# upper.net
KiCad netlist of a schematic drawn in EAGLE
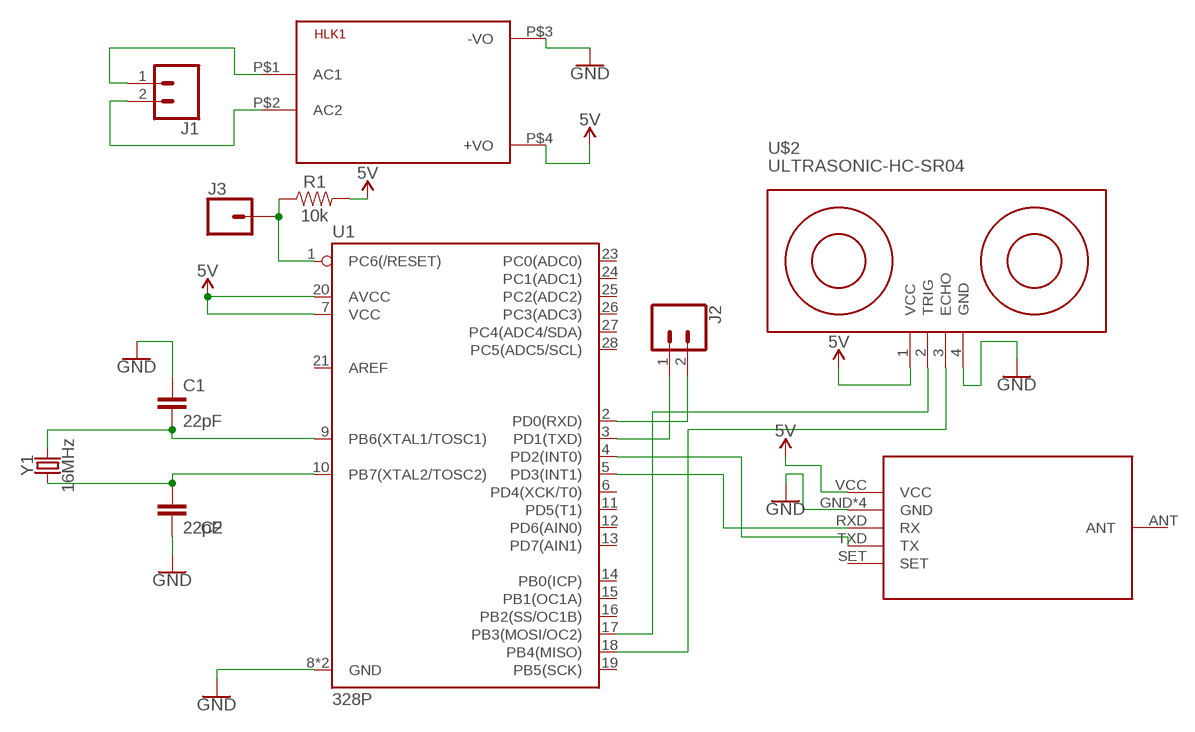
[diagram p0: schematic, sheet 1]

(export (version "E")
  (design (tool "Eeschema 10.0.6"))
  (components
    (comp (ref "C1")
      (value "22pF")
      (footprint "eagle-import:CAP-PTH-2.54")
      (libsource (lib "eagle-import") (part "22PF-PTH-2.54MM-200V-5%"))
    )
    (comp (ref "C2")
      (value "22pF")
      (footprint "eagle-import:CAP-PTH-2.54")
      (libsource (lib "eagle-import") (part "22PF-PTH-2.54MM-200V-5%"))
    )
    (comp (ref "HLK1")
      (value "HLK-PM013W")
      (footprint "eagle-import:HLK-PM01")
      (libsource (lib "eagle-import") (part "HLK-PM013W"))
    )
    (comp (ref "J1")
      (value "CONN_025MM")
      (footprint "eagle-import:SCREWTERMINAL-5MM-2")
      (libsource (lib "eagle-import") (part "CONN_025MM"))
    )
    (comp (ref "J2")
      (value "CONN_025MM")
      (footprint "eagle-import:SCREWTERMINAL-5MM-2")
      (libsource (lib "eagle-import") (part "CONN_025MM"))
    )
    (comp (ref "J3")
      (value "CONN_01")
      (footprint "eagle-import:1X01")
      (libsource (lib "eagle-import") (part "CONN_01"))
    )
    (comp (ref "R1")
      (value "10k")
      (footprint "eagle-import:AXIAL-0.3")
      (libsource (lib "eagle-import") (part "10KOHM-HORIZ-1/4W-1%"))
    )
    (comp (ref "U$1")
      (value "HC-12_FOOTPRINT")
      (footprint "eagle-import:HC-12_FOOTPRINT")
      (libsource (lib "eagle-import") (part "HC-12_FOOTPRINT"))
    )
    (comp (ref "U$2")
      (value "ULTRASONIC-HC-SR04")
      (footprint "eagle-import:ULTRASONIC-HC-SR04")
      (libsource (lib "eagle-import") (part "ULTRASONIC-HC-SR04"))
    )
    (comp (ref "U1")
      (value "328P")
      (footprint "eagle-import:DIP28")
      (libsource (lib "eagle-import") (part "ATMEGA328P_PDIP"))
    )
    (comp (ref "Y1")
      (value "16MHz")
      (footprint "eagle-import:HC49US")
      (libsource (lib "eagle-import") (part "CRYSTAL-16MHZPTH-HC49US"))
    )
  )
  (nets
    (net (code "1") (name "5V") (class "Default")
      (node (ref "HLK1") (pin "P$4") (pinfunction "+VO_P$4") (pintype "bidirectional"))
      (node (ref "R1") (pin "P$2") (pinfunction "2_P$2") (pintype "passive"))
      (node (ref "U$1") (pin "VCC") (pinfunction "VCC_VCC") (pintype "bidirectional"))
      (node (ref "U$2") (pin "1") (pinfunction "VCC_1") (pintype "power_in"))
      (node (ref "U1") (pin "20") (pinfunction "AVCC_20") (pintype "bidirectional"))
      (node (ref "U1") (pin "7") (pinfunction "VCC_7") (pintype "bidirectional"))
    )
    (net (code "2") (name "GND") (class "Default")
      (node (ref "C1") (pin "1") (pinfunction "1_1") (pintype "passive"))
      (node (ref "C2") (pin "2") (pinfunction "2_2") (pintype "passive"))
      (node (ref "HLK1") (pin "P$3") (pinfunction "-VO_P$3") (pintype "bidirectional"))
      (node (ref "U$1") (pin "GND") (pinfunction "GND_GND") (pintype "bidirectional"))
      (node (ref "U$1") (pin "GND1") (pinfunction "GND_GND1") (pintype "bidirectional"))
      (node (ref "U$1") (pin "GND2") (pinfunction "GND_GND2") (pintype "bidirectional"))
      (node (ref "U$1") (pin "MCHFIX") (pinfunction "GND_MCHFIX") (pintype "bidirectional"))
      (node (ref "U$2") (pin "4") (pinfunction "GND_4") (pintype "power_in"))
      (node (ref "U1") (pin "22") (pinfunction "GND_22") (pintype "bidirectional"))
      (node (ref "U1") (pin "8") (pinfunction "GND_8") (pintype "bidirectional"))
    )
    (net (code "3") (name "Net-(HLK1-AC1)") (class "Default")
      (node (ref "HLK1") (pin "P$1") (pinfunction "AC1_P$1") (pintype "bidirectional"))
      (node (ref "J1") (pin "1") (pinfunction "1_1") (pintype "passive"))
    )
    (net (code "4") (name "Net-(HLK1-AC2)") (class "Default")
      (node (ref "HLK1") (pin "P$2") (pinfunction "AC2_P$2") (pintype "bidirectional"))
      (node (ref "J1") (pin "2") (pinfunction "2_2") (pintype "passive"))
    )
    (net (code "5") (name "Net-(R1-1)") (class "Default")
      (node (ref "J3") (pin "1") (pinfunction "1_1") (pintype "passive"))
      (node (ref "R1") (pin "P$1") (pinfunction "1_P$1") (pintype "passive"))
      (node (ref "U1") (pin "1") (pinfunction "PC6(/RESET)_1") (pintype "bidirectional"))
    )
    (net (code "6") (name "Net-(U$1-RX)") (class "Default")
      (node (ref "U$1") (pin "RXD") (pinfunction "RX_RXD") (pintype "bidirectional"))
      (node (ref "U1") (pin "5") (pinfunction "PD3(INT1)_5") (pintype "bidirectional"))
    )
    (net (code "7") (name "Net-(U$1-TX)") (class "Default")
      (node (ref "U$1") (pin "TXD") (pinfunction "TX_TXD") (pintype "bidirectional"))
      (node (ref "U1") (pin "4") (pinfunction "PD2(INT0)_4") (pintype "bidirectional"))
    )
    (net (code "8") (name "Net-(U$2-ECHO)") (class "Default")
      (node (ref "U$2") (pin "3") (pinfunction "ECHO_3") (pintype "output"))
      (node (ref "U1") (pin "18") (pinfunction "PB4(MISO)_18") (pintype "bidirectional"))
    )
    (net (code "9") (name "Net-(U$2-TRIG)") (class "Default")
      (node (ref "U$2") (pin "2") (pinfunction "TRIG_2") (pintype "input"))
      (node (ref "U1") (pin "17") (pinfunction "PB3(MOSI/OC2)_17") (pintype "bidirectional"))
    )
    (net (code "10") (name "Net-(U1-PB6(XTAL1{slash}TOSC1))") (class "Default")
      (node (ref "C1") (pin "2") (pinfunction "2_2") (pintype "passive"))
      (node (ref "U1") (pin "9") (pinfunction "PB6(XTAL1/TOSC1)_9") (pintype "bidirectional"))
      (node (ref "Y1") (pin "2") (pinfunction "2_2") (pintype "passive"))
    )
    (net (code "11") (name "Net-(U1-PB7(XTAL2{slash}TOSC2))") (class "Default")
      (node (ref "C2") (pin "1") (pinfunction "1_1") (pintype "passive"))
      (node (ref "U1") (pin "10") (pinfunction "PB7(XTAL2/TOSC2)_10") (pintype "bidirectional"))
      (node (ref "Y1") (pin "1") (pinfunction "1_1") (pintype "passive"))
    )
    (net (code "12") (name "Net-(U1-PD0(RXD))") (class "Default")
      (node (ref "J2") (pin "2") (pinfunction "2_2") (pintype "passive"))
      (node (ref "U1") (pin "2") (pinfunction "PD0(RXD)_2") (pintype "bidirectional"))
    )
    (net (code "13") (name "Net-(U1-PD1(TXD))") (class "Default")
      (node (ref "J2") (pin "1") (pinfunction "1_1") (pintype "passive"))
      (node (ref "U1") (pin "3") (pinfunction "PD1(TXD)_3") (pintype "bidirectional"))
    )
    (net (code "14") (name "unconnected-(U$1-PadANT)") (class "Default")
      (node (ref "U$1") (pin "ANT") (pinfunction "ANT_ANT") (pintype "bidirectional"))
    )
    (net (code "15") (name "unconnected-(U$1-PadSET)") (class "Default")
      (node (ref "U$1") (pin "SET") (pinfunction "SET_SET") (pintype "bidirectional"))
    )
    (net (code "16") (name "unconnected-(U1-AREF-Pad21)") (class "Default")
      (node (ref "U1") (pin "21") (pinfunction "AREF_21") (pintype "bidirectional"))
    )
    (net (code "17") (name "unconnected-(U1-PB0(ICP)-Pad14)") (class "Default")
      (node (ref "U1") (pin "14") (pinfunction "PB0(ICP)_14") (pintype "bidirectional"))
    )
    (net (code "18") (name "unconnected-(U1-PB1(OC1A)-Pad15)") (class "Default")
      (node (ref "U1") (pin "15") (pinfunction "PB1(OC1A)_15") (pintype "bidirectional"))
    )
    (net (code "19") (name "unconnected-(U1-PB2(SS{slash}OC1B)-Pad16)") (class "Default")
      (node (ref "U1") (pin "16") (pinfunction "PB2(SS/OC1B)_16") (pintype "bidirectional"))
    )
    (net (code "20") (name "unconnected-(U1-PB5(SCK)-Pad19)") (class "Default")
      (node (ref "U1") (pin "19") (pinfunction "PB5(SCK)_19") (pintype "bidirectional"))
    )
    (net (code "21") (name "unconnected-(U1-PC0(ADC0)-Pad23)") (class "Default")
      (node (ref "U1") (pin "23") (pinfunction "PC0(ADC0)_23") (pintype "bidirectional"))
    )
    (net (code "22") (name "unconnected-(U1-PC1(ADC1)-Pad24)") (class "Default")
      (node (ref "U1") (pin "24") (pinfunction "PC1(ADC1)_24") (pintype "bidirectional"))
    )
    (net (code "23") (name "unconnected-(U1-PC2(ADC2)-Pad25)") (class "Default")
      (node (ref "U1") (pin "25") (pinfunction "PC2(ADC2)_25") (pintype "bidirectional"))
    )
    (net (code "24") (name "unconnected-(U1-PC3(ADC3)-Pad26)") (class "Default")
      (node (ref "U1") (pin "26") (pinfunction "PC3(ADC3)_26") (pintype "bidirectional"))
    )
    (net (code "25") (name "unconnected-(U1-PC4(ADC4{slash}SDA)-Pad27)") (class "Default")
      (node (ref "U1") (pin "27") (pinfunction "PC4(ADC4/SDA)_27") (pintype "bidirectional"))
    )
    (net (code "26") (name "unconnected-(U1-PC5(ADC5{slash}SCL)-Pad28)") (class "Default")
      (node (ref "U1") (pin "28") (pinfunction "PC5(ADC5/SCL)_28") (pintype "bidirectional"))
    )
    (net (code "27") (name "unconnected-(U1-PD4(XCK{slash}T0)-Pad6)") (class "Default")
      (node (ref "U1") (pin "6") (pinfunction "PD4(XCK/T0)_6") (pintype "bidirectional"))
    )
    (net (code "28") (name "unconnected-(U1-PD5(T1)-Pad11)") (class "Default")
      (node (ref "U1") (pin "11") (pinfunction "PD5(T1)_11") (pintype "bidirectional"))
    )
    (net (code "29") (name "unconnected-(U1-PD6(AIN0)-Pad12)") (class "Default")
      (node (ref "U1") (pin "12") (pinfunction "PD6(AIN0)_12") (pintype "bidirectional"))
    )
    (net (code "30") (name "unconnected-(U1-PD7(AIN1)-Pad13)") (class "Default")
      (node (ref "U1") (pin "13") (pinfunction "PD7(AIN1)_13") (pintype "bidirectional"))
    )
  )
)
